# MCU3.net
KiCad netlist of a schematic drawn in Altium Designer
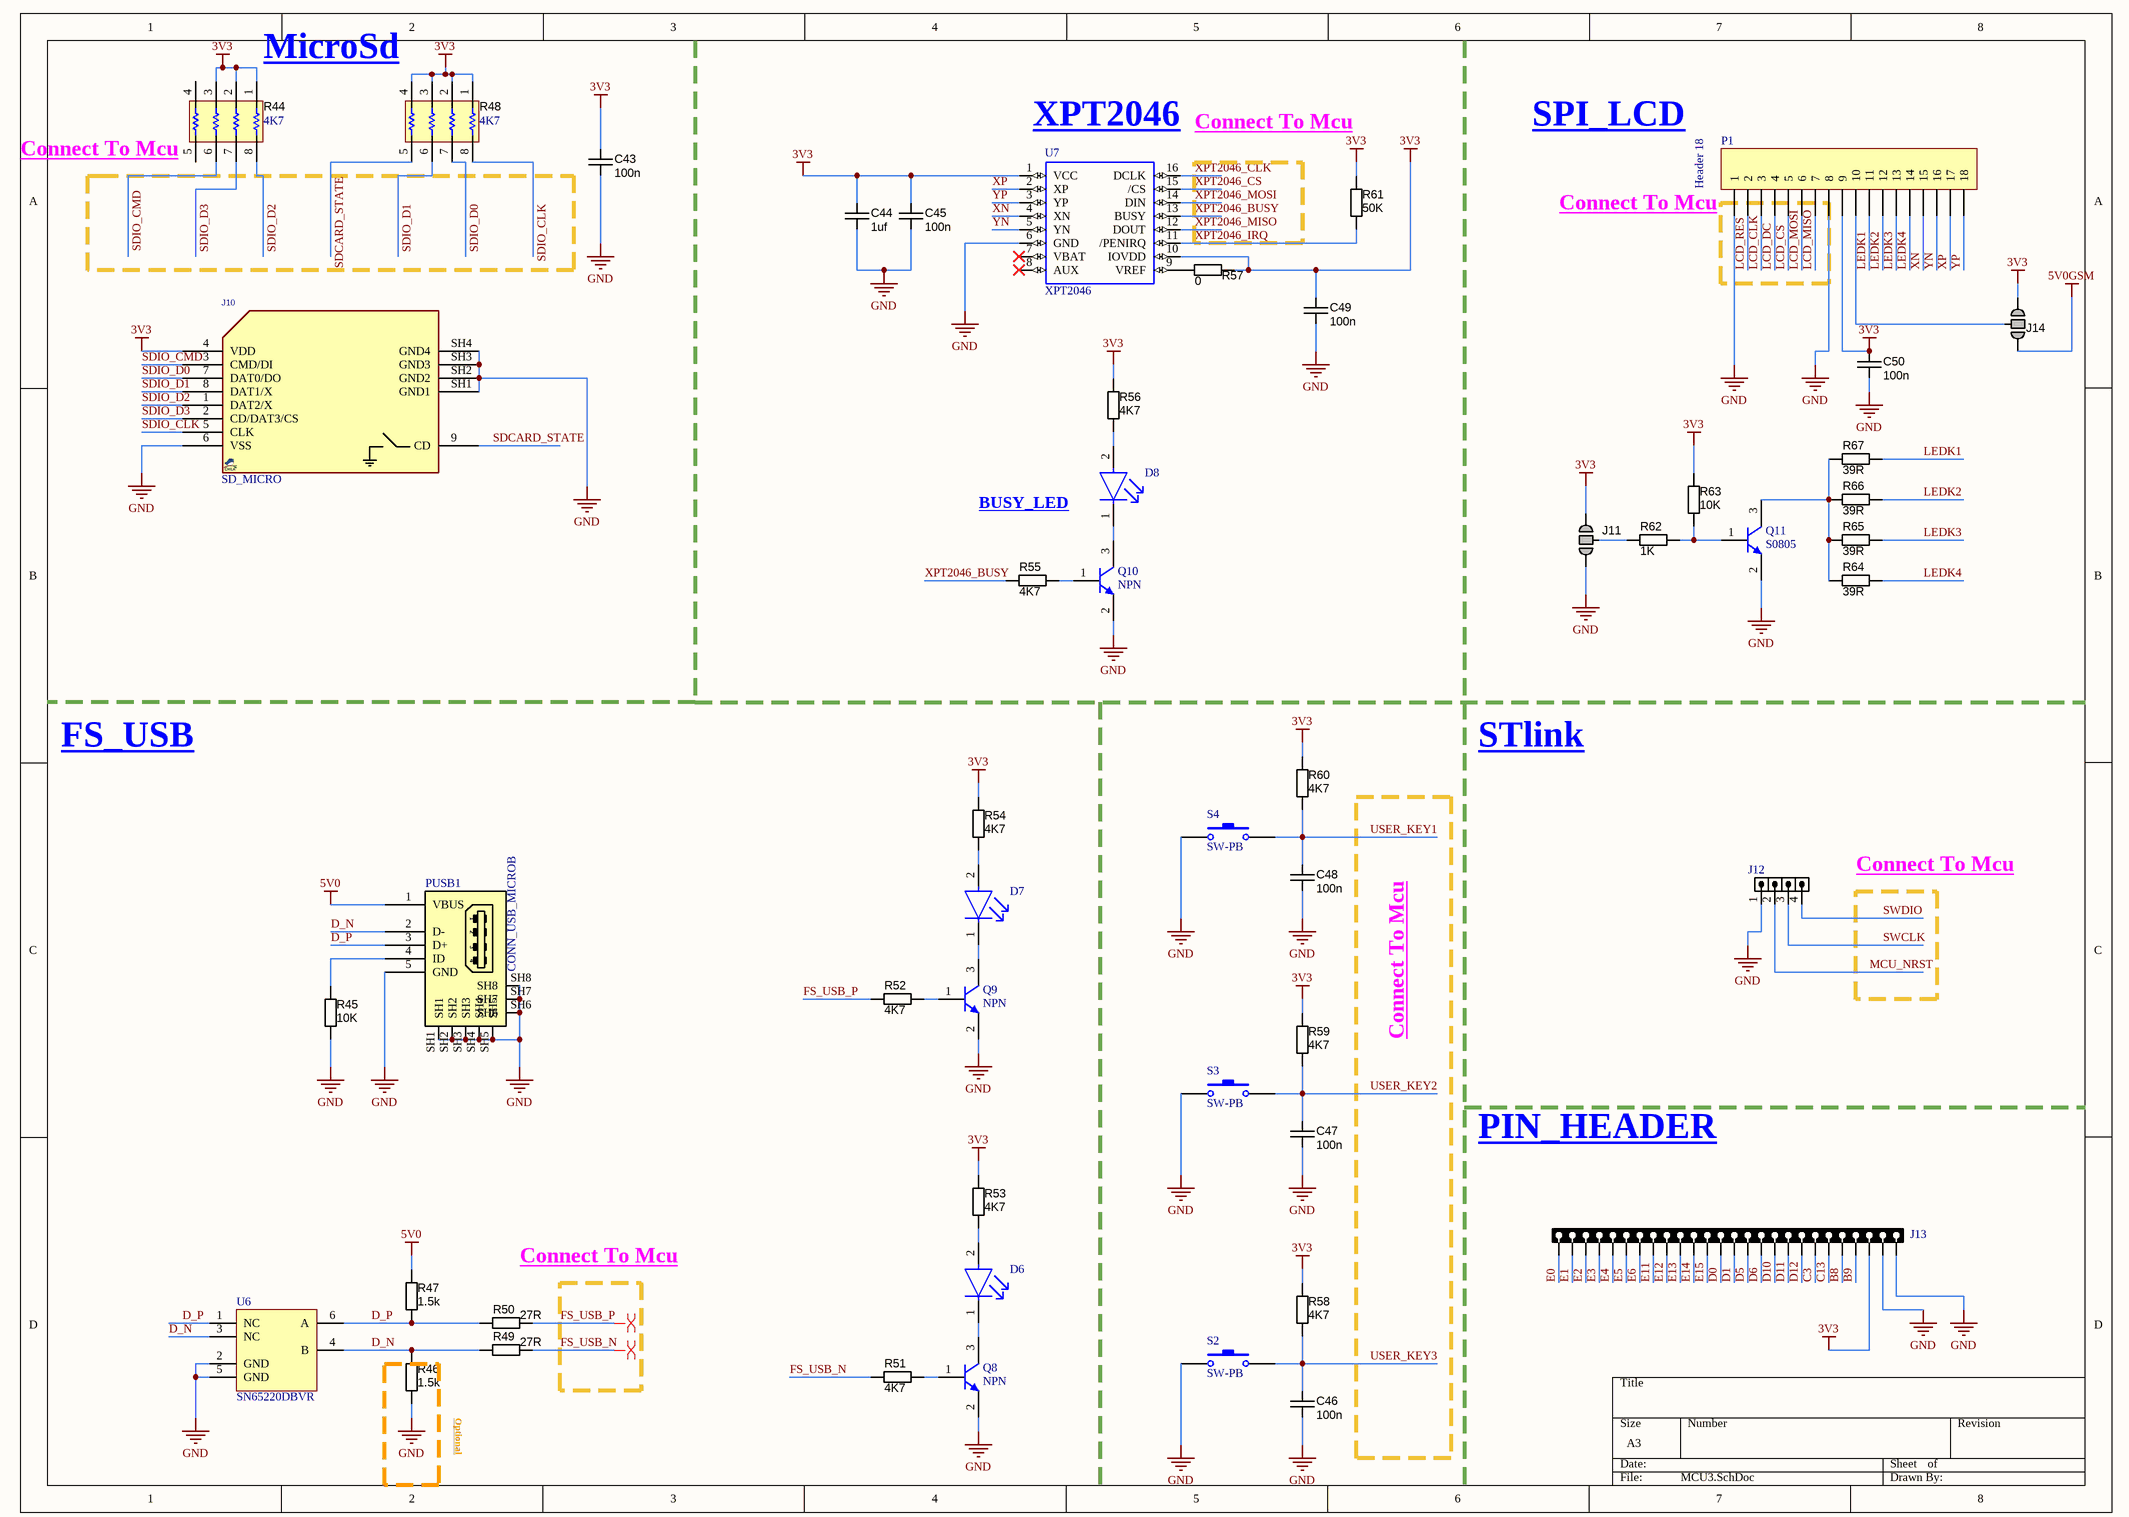
[diagram p0: MCU3.SchDoc]

(export (version "E")
  (design (tool "Eeschema 10.0.6"))
  (components
    (comp (ref "C43")
      (value "100n")
      (footprint "CAPC1608X90N")
      (description "Capacitor SMD Cer 100nF 10% 50V X7R 0603")
      (fields (field (name "TOLERANCE") "±10%") (field (name "Comment") "approved sub OK"))
      (libsource (lib "PBL - Capacitors") (part "CAPC_100n_0603_X7R_50V_10%"))
    )
    (comp (ref "C44")
      (value "1uf")
      (footprint "CAPC3216X180N")
      (description "Capacitor SMD Cer 47nF 10% 50V X7R 1206")
      (fields (field (name "TOLERANCE") "±10%"))
      (libsource (lib "PBL - Capacitors") (part "CAPC_47n_1206_X7R_50V_10%"))
    )
    (comp (ref "C45")
      (value "100n")
      (footprint "CAPC1608X90N")
      (description "Capacitor SMD Cer 100nF 10% 50V X7R 0603")
      (fields (field (name "TOLERANCE") "±10%") (field (name "Comment") "approved sub OK"))
      (libsource (lib "PBL - Capacitors") (part "CAPC_100n_0603_X7R_50V_10%"))
    )
    (comp (ref "C46")
      (value "100n")
      (footprint "CAPC1608X90N")
      (description "Capacitor SMD Cer 100nF 10% 50V X7R 0603")
      (fields (field (name "TOLERANCE") "±10%") (field (name "Comment") "approved sub OK"))
      (libsource (lib "PBL - Capacitors") (part "CAPC_100n_0603_X7R_50V_10%"))
    )
    (comp (ref "C47")
      (value "100n")
      (footprint "CAPC1608X90N")
      (description "Capacitor SMD Cer 100nF 10% 50V X7R 0603")
      (fields (field (name "TOLERANCE") "±10%") (field (name "Comment") "approved sub OK"))
      (libsource (lib "PBL - Capacitors") (part "CAPC_100n_0603_X7R_50V_10%"))
    )
    (comp (ref "C48")
      (value "100n")
      (footprint "CAPC1608X90N")
      (description "Capacitor SMD Cer 100nF 10% 50V X7R 0603")
      (fields (field (name "TOLERANCE") "±10%") (field (name "Comment") "approved sub OK"))
      (libsource (lib "PBL - Capacitors") (part "CAPC_100n_0603_X7R_50V_10%"))
    )
    (comp (ref "C49")
      (value "100n")
      (footprint "CAPC1608X90N")
      (description "Capacitor SMD Cer 100nF 10% 50V X7R 0603")
      (fields (field (name "TOLERANCE") "±10%") (field (name "Comment") "approved sub OK"))
      (libsource (lib "PBL - Capacitors") (part "CAPC_100n_0603_X7R_50V_10%"))
    )
    (comp (ref "C50")
      (value "100n")
      (footprint "CAPC1608X90N")
      (description "Capacitor SMD Cer 100nF 10% 50V X7R 0603")
      (fields (field (name "TOLERANCE") "±10%") (field (name "Comment") "approved sub OK"))
      (libsource (lib "PBL - Capacitors") (part "CAPC_100n_0603_X7R_50V_10%"))
    )
    (comp (ref "D6")
      (value "LTST-C191TBKT")
      (footprint "FP-LTST-C191TBKT-MFG")
      (description "LED BLUE CLEAR CHIP SMD")
      (libsource (lib "Altium Content Vault") (part "8706943c75ba83719d021d2fdc84c58"))
    )
    (comp (ref "D7")
      (value "LTST-C191TBKT")
      (footprint "FP-LTST-C191TBKT-MFG")
      (description "LED BLUE CLEAR CHIP SMD")
      (libsource (lib "Altium Content Vault") (part "8706943c75ba83719d021d2fdc84c58"))
    )
    (comp (ref "D8")
      (value "LTST-C191TBKT")
      (footprint "FP-LTST-C191TBKT-MFG")
      (description "LED BLUE CLEAR CHIP SMD")
      (libsource (lib "Altium Content Vault") (part "8706943c75ba83719d021d2fdc84c58"))
    )
    (comp (ref "J10")
      (value "SD_MICRO")
      (footprint "SDMICRO_AT")
      (description "SD MICRO exist in Iran, Attend 112J-TDAR-R01")
      (fields (field (name "MANF") "Attend") (field (name "MANF_P#") "112J-TDAR-R01"))
      (libsource (lib "socket_card") (part "SOCKET_SDMICRO_AT"))
    )
    (comp (ref "J11")
      (value "Jumper")
      (footprint "Jump_3Way")
      (description "SMD jumper")
      (libsource (lib "PBL - Pads and Jumpers") (part "JUMP_3WAY"))
    )
    (comp (ref "J12")
      (value "HDR1X4")
      (footprint "HDR1X4_2.54mmp")
      (description "CONN, HEADER, Male, pitch: 2.54mm, 4POS")
      (libsource (lib "conn_header_2.54_st") (part "HDR_M_1X4"))
    )
    (comp (ref "J13")
      (value "HDRF26")
      (footprint "HDR 1X26")
      (description "CONN, HEADER, Male, pitch: 2.54mm, 26POS")
      (libsource (lib "Header") (part "HDR_F_1X26"))
    )
    (comp (ref "J14")
      (value "Jumper")
      (footprint "Jump_3Way")
      (description "SMD jumper")
      (libsource (lib "PBL - Pads and Jumpers") (part "JUMP_3WAY"))
    )
    (comp (ref "P1")
      (value "Header 18")
      (footprint "SPI_LCD_18Pin")
      (description "Header, 18-Pin")
      (fields (field (name "PUBLISHER") "Altium Limited"))
      (libsource (lib "Miscellaneous Connectors") (part "Header 18"))
    )
    (comp (ref "PUSB1")
      (value "CONN_USB_MICROB")
      (footprint "USB_MICRO_B_BM_SHS")
      (description "CONN, USB, MICRO B, R/A, SMD, BOTTOM MOUNT")
      (fields (field (name "MANF_P#") "47491-0001") (field (name "MANF") "MOLEX"))
      (libsource (lib "conn_usb") (part "CONN_USB_MICRO_B_MOLEX"))
    )
    (comp (ref "Q8")
      (value "NPN")
      (footprint "SOT23-3")
      (description "NPN Bipolar Transistor")
      (fields (field (name "PUBLISHER") "Altium Limited"))
      (libsource (lib "Miscellaneous Devices") (part "NPN"))
    )
    (comp (ref "Q9")
      (value "NPN")
      (footprint "SOT23-3")
      (description "NPN Bipolar Transistor")
      (fields (field (name "PUBLISHER") "Altium Limited"))
      (libsource (lib "Miscellaneous Devices") (part "NPN"))
    )
    (comp (ref "Q10")
      (value "NPN")
      (footprint "SOT23-3")
      (description "NPN Bipolar Transistor")
      (fields (field (name "PUBLISHER") "Altium Limited"))
      (libsource (lib "Miscellaneous Devices") (part "NPN"))
    )
    (comp (ref "Q11")
      (value "S0805")
      (footprint "SOT23-3")
      (description "NPN Bipolar Transistor")
      (fields (field (name "PUBLISHER") "Altium Limited"))
      (libsource (lib "Miscellaneous Devices") (part "NPN"))
    )
    (comp (ref "R44")
      (value "4K7")
      (footprint "RP0603X4")
      (description "Resistor Array SMD")
      (libsource (lib "Resistor") (part "Resistor Array SMD"))
    )
    (comp (ref "R45")
      (value "10K")
      (footprint "RESC1608X55N")
      (description "Resistor SMD chip 10K Ohm 0.1W 5% 0603")
      (fields (field (name "TOLERANCE") "±5%") (field (name "Comment") "Thick Film"))
      (libsource (lib "PBL - Resistors") (part "RES_4K7_0603_5%"))
    )
    (comp (ref "R46")
      (value "1.5k")
      (footprint "RESC1608X55N")
      (description "Resistor SMD chip 1.5k Ohm 0.1W 5% 0603")
      (fields (field (name "TOLERANCE") "±5%") (field (name "Comment") "Thick Film"))
      (libsource (lib "") (part "RES_4K7_0603_5%_2"))
    )
    (comp (ref "R47")
      (value "1.5k")
      (footprint "RESC1608X55N")
      (description "Resistor SMD chip 1.5k Ohm 0.1W 5% 0603")
      (fields (field (name "TOLERANCE") "±5%") (field (name "Comment") "Thick Film"))
      (libsource (lib "") (part "RES_4K7_0603_5%_2"))
    )
    (comp (ref "R48")
      (value "4K7")
      (footprint "RP0603X4")
      (description "Resistor Array SMD")
      (libsource (lib "Resistor") (part "Resistor Array SMD"))
    )
    (comp (ref "R49")
      (value "27R")
      (footprint "RESC1608X55N")
      (description "Resistor SMD chip 27 Ohm 0.1W 5% 0603")
      (fields (field (name "TOLERANCE") "±5%") (field (name "Comment") "Thick Film"))
      (libsource (lib "PBL - Resistors") (part "RES_4K7_0603_5%"))
    )
    (comp (ref "R50")
      (value "27R")
      (footprint "RESC1608X55N")
      (description "Resistor SMD chip 27 Ohm 0.1W 5% 0603")
      (fields (field (name "TOLERANCE") "±5%") (field (name "Comment") "Thick Film"))
      (libsource (lib "PBL - Resistors") (part "RES_4K7_0603_5%"))
    )
    (comp (ref "R51")
      (value "4K7")
      (footprint "RESC1608X55N")
      (description "Resistor SMD chip 4.7k Ohm 0.1W 5% 0603")
      (fields (field (name "TOLERANCE") "±5%") (field (name "Comment") "Thick Film"))
      (libsource (lib "") (part "RES_4K7_0603_5%_1"))
    )
    (comp (ref "R52")
      (value "4K7")
      (footprint "RESC1608X55N")
      (description "Resistor SMD chip 4.7k Ohm 0.1W 5% 0603")
      (fields (field (name "TOLERANCE") "±5%") (field (name "Comment") "Thick Film"))
      (libsource (lib "") (part "RES_4K7_0603_5%_1"))
    )
    (comp (ref "R53")
      (value "4K7")
      (footprint "RESC1608X55N")
      (description "Resistor SMD chip 4.7k Ohm 0.1W 5% 0603")
      (fields (field (name "TOLERANCE") "±5%") (field (name "Comment") "Thick Film"))
      (libsource (lib "PBL - Resistors") (part "RES_4K7_0603_5%"))
    )
    (comp (ref "R54")
      (value "4K7")
      (footprint "RESC1608X55N")
      (description "Resistor SMD chip 4.7k Ohm 0.1W 5% 0603")
      (fields (field (name "TOLERANCE") "±5%") (field (name "Comment") "Thick Film"))
      (libsource (lib "PBL - Resistors") (part "RES_4K7_0603_5%"))
    )
    (comp (ref "R55")
      (value "4K7")
      (footprint "RESC1608X55N")
      (description "Resistor SMD chip 4.7k Ohm 0.1W 5% 0603")
      (fields (field (name "TOLERANCE") "±5%") (field (name "Comment") "Thick Film"))
      (libsource (lib "") (part "RES_4K7_0603_5%_1"))
    )
    (comp (ref "R56")
      (value "4K7")
      (footprint "RESC1608X55N")
      (description "Resistor SMD chip 4.7k Ohm 0.1W 5% 0603")
      (fields (field (name "TOLERANCE") "±5%") (field (name "Comment") "Thick Film"))
      (libsource (lib "PBL - Resistors") (part "RES_4K7_0603_5%"))
    )
    (comp (ref "R57")
      (value "0")
      (footprint "RESC1608X55N")
      (description "Resistor SMD chip 0 Ohm 0.1W 5% 0603")
      (fields (field (name "TOLERANCE") "±5%") (field (name "Comment") "Thick Film"))
      (libsource (lib "") (part "RES_4K7_0603_5%_2"))
    )
    (comp (ref "R58")
      (value "4K7")
      (footprint "RESC1608X55N")
      (description "Resistor SMD chip 4.7k Ohm 0.1W 5% 0603")
      (fields (field (name "TOLERANCE") "±5%") (field (name "Comment") "Thick Film"))
      (libsource (lib "") (part "RES_4K7_0603_5%_2"))
    )
    (comp (ref "R59")
      (value "4K7")
      (footprint "RESC1608X55N")
      (description "Resistor SMD chip 4.7k Ohm 0.1W 5% 0603")
      (fields (field (name "TOLERANCE") "±5%") (field (name "Comment") "Thick Film"))
      (libsource (lib "") (part "RES_4K7_0603_5%_2"))
    )
    (comp (ref "R60")
      (value "4K7")
      (footprint "RESC1608X55N")
      (description "Resistor SMD chip 4.7k Ohm 0.1W 5% 0603")
      (fields (field (name "TOLERANCE") "±5%") (field (name "Comment") "Thick Film"))
      (libsource (lib "") (part "RES_4K7_0603_5%_2"))
    )
    (comp (ref "R61")
      (value "50K")
      (footprint "RESC1608X55N")
      (description "Resistor SMD chip 10K Ohm 0.1W 5% 0603")
      (fields (field (name "TOLERANCE") "±5%") (field (name "Comment") "Thick Film"))
      (libsource (lib "") (part "RES_4K7_0603_5%_3"))
    )
    (comp (ref "R62")
      (value "1K")
      (footprint "RESC1608X55N")
      (description "Resistor SMD chip 1K Ohm 0.1W 5% 0603")
      (fields (field (name "TOLERANCE") "±5%") (field (name "Comment") "Thick Film"))
      (libsource (lib "") (part "RES_4K7_0603_5%_2"))
    )
    (comp (ref "R63")
      (value "10K")
      (footprint "RESC1608X55N")
      (description "Resistor SMD chip 10K Ohm 0.1W 5% 0603")
      (fields (field (name "TOLERANCE") "±5%") (field (name "Comment") "Thick Film"))
      (libsource (lib "PBL - Resistors") (part "RES_4K7_0603_5%"))
    )
    (comp (ref "R64")
      (value "39R")
      (footprint "RESC1608X55N")
      (description "Resistor SMD chip 39R Ohm 0.1W 5% 0603")
      (fields (field (name "TOLERANCE") "±5%") (field (name "Comment") "Thick Film"))
      (libsource (lib "") (part "RES_4K7_0603_5%_1"))
    )
    (comp (ref "R65")
      (value "39R")
      (footprint "RESC1608X55N")
      (description "Resistor SMD chip 39R Ohm 0.1W 5% 0603")
      (fields (field (name "TOLERANCE") "±5%") (field (name "Comment") "Thick Film"))
      (libsource (lib "") (part "RES_4K7_0603_5%_1"))
    )
    (comp (ref "R66")
      (value "39R")
      (footprint "RESC1608X55N")
      (description "Resistor SMD chip 39R Ohm 0.1W 5% 0603")
      (fields (field (name "TOLERANCE") "±5%") (field (name "Comment") "Thick Film"))
      (libsource (lib "") (part "RES_4K7_0603_5%_1"))
    )
    (comp (ref "R67")
      (value "39R")
      (footprint "RESC1608X55N")
      (description "Resistor SMD chip 39R Ohm 0.1W 5% 0603")
      (fields (field (name "TOLERANCE") "±5%") (field (name "Comment") "Thick Film"))
      (libsource (lib "") (part "RES_4K7_0603_5%_1"))
    )
    (comp (ref "S2")
      (value "SW-PB")
      (footprint "SWPBS_SPST_6X3X5")
      (description "Switch")
      (fields (field (name "PUBLISHER") "Altium Limited"))
      (libsource (lib "Miscellaneous Devices") (part "SW-PB"))
    )
    (comp (ref "S3")
      (value "SW-PB")
      (footprint "SWPBS_SPST_6X3X5")
      (description "Switch")
      (fields (field (name "PUBLISHER") "Altium Limited"))
      (libsource (lib "Miscellaneous Devices") (part "SW-PB"))
    )
    (comp (ref "S4")
      (value "SW-PB")
      (footprint "SWPBS_SPST_6X3X5")
      (description "Switch")
      (fields (field (name "PUBLISHER") "Altium Limited"))
      (libsource (lib "Miscellaneous Devices") (part "SW-PB"))
    )
    (comp (ref "U6")
      (value "SN65220DBVR")
      (footprint "DBV0006A_M")
      (fields (field (name "MANUFACTURER") "Texas Instruments"))
      (libsource (lib "Altium Content Vault") (part "TI-SN65220-SOT-23_DBV-6"))
    )
    (comp (ref "U7")
      (value "XPT2046")
      (footprint "TSSOP16")
      (description "RASPBERRY PI 3.5 TFT DISPLAY")
      (fields (field (name "MF") "Xptek"))
      (libsource (lib "XPT2046") (part "XPT2046"))
    )
  )
  (nets
    (net (code "2") (name "/B8") (class "Default")
      (node (ref "J13") (pin "22") (pinfunction "22_22") (pintype "passive"))
    )
    (net (code "3") (name "/B9") (class "Default")
      (node (ref "J13") (pin "23") (pinfunction "23_23") (pintype "passive"))
    )
    (net (code "4") (name "/C3") (class "Default")
      (node (ref "J13") (pin "20") (pinfunction "20_20") (pintype "passive"))
    )
    (net (code "5") (name "/C13") (class "Default")
      (node (ref "J13") (pin "21") (pinfunction "21_21") (pintype "passive"))
    )
    (net (code "6") (name "/D0") (class "Default")
      (node (ref "J13") (pin "13") (pinfunction "13_13") (pintype "passive"))
    )
    (net (code "7") (name "/D1") (class "Default")
      (node (ref "J13") (pin "14") (pinfunction "14_14") (pintype "passive"))
    )
    (net (code "8") (name "/D5") (class "Default")
      (node (ref "J13") (pin "15") (pinfunction "15_15") (pintype "passive"))
    )
    (net (code "9") (name "/D6") (class "Default")
      (node (ref "J13") (pin "16") (pinfunction "16_16") (pintype "passive"))
    )
    (net (code "10") (name "/D10") (class "Default")
      (node (ref "J13") (pin "17") (pinfunction "17_17") (pintype "passive"))
    )
    (net (code "11") (name "/D11") (class "Default")
      (node (ref "J13") (pin "18") (pinfunction "18_18") (pintype "passive"))
    )
    (net (code "12") (name "/D12") (class "Default")
      (node (ref "J13") (pin "19") (pinfunction "19_19") (pintype "passive"))
    )
    (net (code "13") (name "/D_N") (class "Default")
      (node (ref "PUSB1") (pin "2") (pinfunction "D-_2") (pintype "passive"))
      (node (ref "R46") (pin "1") (pinfunction "1_1") (pintype "passive"))
      (node (ref "R49") (pin "1") (pinfunction "1_1") (pintype "passive"))
      (node (ref "U6") (pin "3") (pinfunction "NC_3") (pintype "passive"))
      (node (ref "U6") (pin "4") (pinfunction "B_4") (pintype "passive"))
    )
    (net (code "14") (name "/D_P") (class "Default")
      (node (ref "PUSB1") (pin "3") (pinfunction "D+_3") (pintype "passive"))
      (node (ref "R47") (pin "2") (pinfunction "2_2") (pintype "passive"))
      (node (ref "R50") (pin "1") (pinfunction "1_1") (pintype "passive"))
      (node (ref "U6") (pin "1") (pinfunction "NC_1") (pintype "passive"))
      (node (ref "U6") (pin "6") (pinfunction "A_6") (pintype "passive"))
    )
    (net (code "15") (name "/E0") (class "Default")
      (node (ref "J13") (pin "1") (pinfunction "1_1") (pintype "passive"))
    )
    (net (code "16") (name "/E1") (class "Default")
      (node (ref "J13") (pin "2") (pinfunction "2_2") (pintype "passive"))
    )
    (net (code "17") (name "/E2") (class "Default")
      (node (ref "J13") (pin "3") (pinfunction "3_3") (pintype "passive"))
    )
    (net (code "18") (name "/E3") (class "Default")
      (node (ref "J13") (pin "4") (pinfunction "4_4") (pintype "passive"))
    )
    (net (code "19") (name "/E4") (class "Default")
      (node (ref "J13") (pin "5") (pinfunction "5_5") (pintype "passive"))
    )
    (net (code "20") (name "/E5") (class "Default")
      (node (ref "J13") (pin "6") (pinfunction "6_6") (pintype "passive"))
    )
    (net (code "21") (name "/E6") (class "Default")
      (node (ref "J13") (pin "7") (pinfunction "7_7") (pintype "passive"))
    )
    (net (code "22") (name "/E11") (class "Default")
      (node (ref "J13") (pin "8") (pinfunction "8_8") (pintype "passive"))
    )
    (net (code "23") (name "/E12") (class "Default")
      (node (ref "J13") (pin "9") (pinfunction "9_9") (pintype "passive"))
    )
    (net (code "24") (name "/E13") (class "Default")
      (node (ref "J13") (pin "10") (pinfunction "10_10") (pintype "passive"))
    )
    (net (code "25") (name "/E14") (class "Default")
      (node (ref "J13") (pin "11") (pinfunction "11_11") (pintype "passive"))
    )
    (net (code "26") (name "/E15") (class "Default")
      (node (ref "J13") (pin "12") (pinfunction "12_12") (pintype "passive"))
    )
    (net (code "27") (name "/FS_USB_N") (class "Default")
      (node (ref "R49") (pin "2") (pinfunction "2_2") (pintype "passive"))
      (node (ref "R51") (pin "1") (pinfunction "1_1") (pintype "passive"))
    )
    (net (code "28") (name "/FS_USB_P") (class "Default")
      (node (ref "R50") (pin "2") (pinfunction "2_2") (pintype "passive"))
      (node (ref "R52") (pin "1") (pinfunction "1_1") (pintype "passive"))
    )
    (net (code "29") (name "/LCD_CLK") (class "Default")
      (node (ref "P1") (pin "3") (pinfunction "3_3") (pintype "passive"))
    )
    (net (code "30") (name "/LCD_CS") (class "Default")
      (node (ref "P1") (pin "5") (pinfunction "5_5") (pintype "passive"))
    )
    (net (code "31") (name "/LCD_DC") (class "Default")
      (node (ref "P1") (pin "4") (pinfunction "4_4") (pintype "passive"))
    )
    (net (code "32") (name "/LCD_MISO") (class "Default")
      (node (ref "P1") (pin "7") (pinfunction "7_7") (pintype "passive"))
    )
    (net (code "33") (name "/LCD_MOSI") (class "Default")
      (node (ref "P1") (pin "6") (pinfunction "6_6") (pintype "passive"))
    )
    (net (code "34") (name "/LCD_RES") (class "Default")
      (node (ref "P1") (pin "2") (pinfunction "2_2") (pintype "passive"))
    )
    (net (code "35") (name "/LEDK1") (class "Default")
      (node (ref "P1") (pin "11") (pinfunction "11_11") (pintype "passive"))
      (node (ref "R67") (pin "2") (pinfunction "2_2") (pintype "passive"))
    )
    (net (code "36") (name "/LEDK2") (class "Default")
      (node (ref "P1") (pin "12") (pinfunction "12_12") (pintype "passive"))
      (node (ref "R66") (pin "2") (pinfunction "2_2") (pintype "passive"))
    )
    (net (code "37") (name "/LEDK3") (class "Default")
      (node (ref "P1") (pin "13") (pinfunction "13_13") (pintype "passive"))
      (node (ref "R65") (pin "2") (pinfunction "2_2") (pintype "passive"))
    )
    (net (code "38") (name "/LEDK4") (class "Default")
      (node (ref "P1") (pin "14") (pinfunction "14_14") (pintype "passive"))
      (node (ref "R64") (pin "2") (pinfunction "2_2") (pintype "passive"))
    )
    (net (code "39") (name "/MCU_NRST") (class "Default")
      (node (ref "J12") (pin "2") (pinfunction "2_2") (pintype "passive"))
    )
    (net (code "40") (name "/SDCARD_STATE") (class "Default")
      (node (ref "J10") (pin "9") (pinfunction "CD_9") (pintype "passive"))
      (node (ref "R48") (pin "5") (pinfunction "5_5") (pintype "passive"))
    )
    (net (code "41") (name "/SDIO_CLK") (class "Default")
      (node (ref "J10") (pin "5") (pinfunction "CLK_5") (pintype "passive"))
      (node (ref "R48") (pin "8") (pinfunction "8_8") (pintype "passive"))
    )
    (net (code "42") (name "/SDIO_CMD") (class "Default")
      (node (ref "J10") (pin "3") (pinfunction "CMD/DI_3") (pintype "passive"))
      (node (ref "R44") (pin "6") (pinfunction "6_6") (pintype "passive"))
    )
    (net (code "43") (name "/SDIO_D0") (class "Default")
      (node (ref "J10") (pin "7") (pinfunction "DAT0/DO_7") (pintype "passive"))
      (node (ref "R48") (pin "7") (pinfunction "7_7") (pintype "passive"))
    )
    (net (code "44") (name "/SDIO_D1") (class "Default")
      (node (ref "J10") (pin "8") (pinfunction "DAT1/X_8") (pintype "passive"))
      (node (ref "R48") (pin "6") (pinfunction "6_6") (pintype "passive"))
    )
    (net (code "45") (name "/SDIO_D2") (class "Default")
      (node (ref "J10") (pin "1") (pinfunction "DAT2/X_1") (pintype "passive"))
      (node (ref "R44") (pin "8") (pinfunction "8_8") (pintype "passive"))
    )
    (net (code "46") (name "/SDIO_D3") (class "Default")
      (node (ref "J10") (pin "2") (pinfunction "CD/DAT3/CS_2") (pintype "passive"))
      (node (ref "R44") (pin "7") (pinfunction "7_7") (pintype "passive"))
    )
    (net (code "47") (name "/SWCLK") (class "Default")
      (node (ref "J12") (pin "3") (pinfunction "3_3") (pintype "passive"))
    )
    (net (code "48") (name "/SWDIO") (class "Default")
      (node (ref "J12") (pin "4") (pinfunction "4_4") (pintype "passive"))
    )
    (net (code "49") (name "/USER_KEY1") (class "Default")
      (node (ref "C48") (pin "1") (pintype "passive"))
      (node (ref "R60") (pin "2") (pinfunction "2_2") (pintype "passive"))
      (node (ref "S4") (pin "1") (pinfunction "1_1") (pintype "passive"))
    )
    (net (code "50") (name "/USER_KEY2") (class "Default")
      (node (ref "C47") (pin "1") (pintype "passive"))
      (node (ref "R59") (pin "2") (pinfunction "2_2") (pintype "passive"))
      (node (ref "S3") (pin "1") (pinfunction "1_1") (pintype "passive"))
    )
    (net (code "51") (name "/USER_KEY3") (class "Default")
      (node (ref "C46") (pin "1") (pintype "passive"))
      (node (ref "R58") (pin "2") (pinfunction "2_2") (pintype "passive"))
      (node (ref "S2") (pin "1") (pinfunction "1_1") (pintype "passive"))
    )
    (net (code "52") (name "/XN") (class "Default")
      (node (ref "P1") (pin "15") (pinfunction "15_15") (pintype "passive"))
      (node (ref "U7") (pin "4") (pinfunction "XN_4") (pintype "bidirectional"))
    )
    (net (code "53") (name "/XP") (class "Default")
      (node (ref "P1") (pin "17") (pinfunction "17_17") (pintype "passive"))
      (node (ref "U7") (pin "2") (pinfunction "XP_2") (pintype "bidirectional"))
    )
    (net (code "54") (name "/XPT2046_BUSY") (class "Default")
      (node (ref "R55") (pin "1") (pinfunction "1_1") (pintype "passive"))
      (node (ref "U7") (pin "13") (pinfunction "BUSY_13") (pintype "bidirectional"))
    )
    (net (code "55") (name "/XPT2046_CLK") (class "Default")
      (node (ref "U7") (pin "16") (pinfunction "DCLK_16") (pintype "bidirectional"))
    )
    (net (code "56") (name "/XPT2046_CS") (class "Default")
      (node (ref "U7") (pin "15") (pinfunction "/CS_15") (pintype "bidirectional"))
    )
    (net (code "57") (name "/XPT2046_IRQ") (class "Default")
      (node (ref "R61") (pin "2") (pinfunction "2_2") (pintype "passive"))
      (node (ref "U7") (pin "11") (pinfunction "/PENIRQ_11") (pintype "bidirectional"))
    )
    (net (code "58") (name "/XPT2046_MISO") (class "Default")
      (node (ref "U7") (pin "12") (pinfunction "DOUT_12") (pintype "bidirectional"))
    )
    (net (code "59") (name "/XPT2046_MOSI") (class "Default")
      (node (ref "U7") (pin "14") (pinfunction "DIN_14") (pintype "bidirectional"))
    )
    (net (code "60") (name "/YN") (class "Default")
      (node (ref "P1") (pin "16") (pinfunction "16_16") (pintype "passive"))
      (node (ref "U7") (pin "5") (pinfunction "YN_5") (pintype "bidirectional"))
    )
    (net (code "61") (name "/YP") (class "Default")
      (node (ref "P1") (pin "18") (pinfunction "18_18") (pintype "passive"))
      (node (ref "U7") (pin "3") (pinfunction "YP_3") (pintype "bidirectional"))
    )
    (net (code "62") (name "3V3") (class "Default")
      (node (ref "C43") (pin "1") (pintype "passive"))
      (node (ref "C44") (pin "1") (pintype "passive"))
      (node (ref "C45") (pin "1") (pintype "passive"))
      (node (ref "C49") (pin "1") (pintype "passive"))
      (node (ref "C50") (pin "1") (pintype "passive"))
      (node (ref "J10") (pin "4") (pinfunction "VDD_4") (pintype "passive"))
      (node (ref "J11") (pin "3") (pinfunction "3_3") (pintype "passive"))
      (node (ref "J13") (pin "24") (pinfunction "24_24") (pintype "passive"))
      (node (ref "J14") (pin "1") (pinfunction "1_1") (pintype "passive"))
      (node (ref "P1") (pin "9") (pinfunction "9_9") (pintype "passive"))
      (node (ref "R44") (pin "1") (pinfunction "1_1") (pintype "passive"))
      (node (ref "R44") (pin "2") (pinfunction "2_2") (pintype "passive"))
      (node (ref "R44") (pin "3") (pinfunction "3_3") (pintype "passive"))
      (node (ref "R48") (pin "1") (pinfunction "1_1") (pintype "passive"))
      (node (ref "R48") (pin "2") (pinfunction "2_2") (pintype "passive"))
      (node (ref "R48") (pin "3") (pinfunction "3_3") (pintype "passive"))
      (node (ref "R48") (pin "4") (pinfunction "4_4") (pintype "passive"))
      (node (ref "R53") (pin "2") (pinfunction "2_2") (pintype "passive"))
      (node (ref "R54") (pin "2") (pinfunction "2_2") (pintype "passive"))
      (node (ref "R56") (pin "2") (pinfunction "2_2") (pintype "passive"))
      (node (ref "R57") (pin "1") (pinfunction "1_1") (pintype "passive"))
      (node (ref "R58") (pin "1") (pinfunction "1_1") (pintype "passive"))
      (node (ref "R59") (pin "1") (pinfunction "1_1") (pintype "passive"))
      (node (ref "R60") (pin "1") (pinfunction "1_1") (pintype "passive"))
      (node (ref "R61") (pin "1") (pinfunction "1_1") (pintype "passive"))
      (node (ref "R63") (pin "2") (pinfunction "2_2") (pintype "passive"))
      (node (ref "U7") (pin "1") (pinfunction "VCC_1") (pintype "bidirectional"))
      (node (ref "U7") (pin "10") (pinfunction "IOVDD_10") (pintype "bidirectional"))
    )
    (net (code "63") (name "5V0") (class "Default")
      (node (ref "PUSB1") (pin "1") (pinfunction "VBUS_1") (pintype "power_in"))
      (node (ref "R47") (pin "1") (pinfunction "1_1") (pintype "passive"))
    )
    (net (code "64") (name "5V0GSM") (class "Default")
      (node (ref "J14") (pin "3") (pinfunction "3_3") (pintype "passive"))
    )
    (net (code "65") (name "GND") (class "Default")
      (node (ref "C43") (pin "2") (pintype "passive"))
      (node (ref "C44") (pin "2") (pintype "passive"))
      (node (ref "C45") (pin "2") (pintype "passive"))
      (node (ref "C46") (pin "2") (pintype "passive"))
      (node (ref "C47") (pin "2") (pintype "passive"))
      (node (ref "C48") (pin "2") (pintype "passive"))
      (node (ref "C49") (pin "2") (pintype "passive"))
      (node (ref "C50") (pin "2") (pintype "passive"))
      (node (ref "J10") (pin "6") (pinfunction "VSS_6") (pintype "passive"))
      (node (ref "J10") (pin "SH1") (pinfunction "GND1_SH1") (pintype "passive"))
      (node (ref "J10") (pin "SH2") (pinfunction "GND2_SH2") (pintype "passive"))
      (node (ref "J10") (pin "SH3") (pinfunction "GND3_SH3") (pintype "passive"))
      (node (ref "J10") (pin "SH4") (pinfunction "GND4_SH4") (pintype "passive"))
      (node (ref "J11") (pin "1") (pinfunction "1_1") (pintype "passive"))
      (node (ref "J12") (pin "1") (pinfunction "1_1") (pintype "passive"))
      (node (ref "J13") (pin "25") (pinfunction "25_25") (pintype "passive"))
      (node (ref "J13") (pin "26") (pinfunction "26_26") (pintype "passive"))
      (node (ref "P1") (pin "1") (pinfunction "1_1") (pintype "passive"))
      (node (ref "P1") (pin "8") (pinfunction "8_8") (pintype "passive"))
      (node (ref "PUSB1") (pin "5") (pinfunction "GND_5") (pintype "power_in"))
      (node (ref "PUSB1") (pin "SH1") (pinfunction "SH1_SH1") (pintype "passive"))
      (node (ref "PUSB1") (pin "SH2") (pinfunction "SH2_SH2") (pintype "passive"))
      (node (ref "PUSB1") (pin "SH3") (pinfunction "SH3_SH3") (pintype "passive"))
      (node (ref "PUSB1") (pin "SH4") (pinfunction "SH4_SH4") (pintype "passive"))
      (node (ref "PUSB1") (pin "SH5") (pinfunction "SH5_SH5") (pintype "passive"))
      (node (ref "PUSB1") (pin "SH6") (pinfunction "SH6_SH6") (pintype "passive"))
      (node (ref "PUSB1") (pin "SH7") (pinfunction "SH7_SH7") (pintype "passive"))
      (node (ref "PUSB1") (pin "SH8") (pinfunction "SH8_SH8") (pintype "passive"))
      (node (ref "Q10") (pin "2") (pinfunction "E_2") (pintype "passive"))
      (node (ref "Q11") (pin "2") (pinfunction "E_2") (pintype "passive"))
      (node (ref "Q8") (pin "2") (pinfunction "E_2") (pintype "passive"))
      (node (ref "Q9") (pin "2") (pinfunction "E_2") (pintype "passive"))
      (node (ref "R45") (pin "1") (pinfunction "1_1") (pintype "passive"))
      (node (ref "R46") (pin "2") (pinfunction "2_2") (pintype "passive"))
      (node (ref "S2") (pin "2") (pinfunction "2_2") (pintype "passive"))
      (node (ref "S3") (pin "2") (pinfunction "2_2") (pintype "passive"))
      (node (ref "S4") (pin "2") (pinfunction "2_2") (pintype "passive"))
      (node (ref "U6") (pin "2") (pinfunction "GND_2") (pintype "power_in"))
      (node (ref "U6") (pin "5") (pinfunction "GND_5") (pintype "power_in"))
      (node (ref "U7") (pin "6") (pinfunction "GND_6") (pintype "bidirectional"))
    )
    (net (code "66") (name "Net-(D6-A)") (class "Default")
      (node (ref "D6") (pin "2") (pinfunction "A_2") (pintype "passive"))
      (node (ref "R53") (pin "1") (pinfunction "1_1") (pintype "passive"))
    )
    (net (code "67") (name "Net-(D6-C)") (class "Default")
      (node (ref "D6") (pin "1") (pinfunction "C_1") (pintype "passive"))
      (node (ref "Q8") (pin "3") (pinfunction "C_3") (pintype "passive"))
    )
    (net (code "68") (name "Net-(D7-A)") (class "Default")
      (node (ref "D7") (pin "2") (pinfunction "A_2") (pintype "passive"))
      (node (ref "R54") (pin "1") (pinfunction "1_1") (pintype "passive"))
    )
    (net (code "69") (name "Net-(D7-C)") (class "Default")
      (node (ref "D7") (pin "1") (pinfunction "C_1") (pintype "passive"))
      (node (ref "Q9") (pin "3") (pinfunction "C_3") (pintype "passive"))
    )
    (net (code "70") (name "Net-(D8-A)") (class "Default")
      (node (ref "D8") (pin "2") (pinfunction "A_2") (pintype "passive"))
      (node (ref "R56") (pin "1") (pinfunction "1_1") (pintype "passive"))
    )
    (net (code "71") (name "Net-(D8-C)") (class "Default")
      (node (ref "D8") (pin "1") (pinfunction "C_1") (pintype "passive"))
      (node (ref "Q10") (pin "3") (pinfunction "C_3") (pintype "passive"))
    )
    (net (code "72") (name "Net-(J11-Pad2)") (class "Default")
      (node (ref "J11") (pin "2") (pinfunction "2_2") (pintype "passive"))
      (node (ref "R62") (pin "2") (pinfunction "2_2") (pintype "passive"))
    )
    (net (code "73") (name "Net-(J14-Pad2)") (class "Default")
      (node (ref "J14") (pin "2") (pinfunction "2_2") (pintype "passive"))
      (node (ref "P1") (pin "10") (pinfunction "10_10") (pintype "passive"))
    )
    (net (code "74") (name "Net-(PUSB1-ID)") (class "Default")
      (node (ref "PUSB1") (pin "4") (pinfunction "ID_4") (pintype "power_in"))
      (node (ref "R45") (pin "2") (pinfunction "2_2") (pintype "passive"))
    )
    (net (code "75") (name "Net-(Q8-B)") (class "Default")
      (node (ref "Q8") (pin "1") (pinfunction "B_1") (pintype "passive"))
      (node (ref "R51") (pin "2") (pinfunction "2_2") (pintype "passive"))
    )
    (net (code "76") (name "Net-(Q9-B)") (class "Default")
      (node (ref "Q9") (pin "1") (pinfunction "B_1") (pintype "passive"))
      (node (ref "R52") (pin "2") (pinfunction "2_2") (pintype "passive"))
    )
    (net (code "77") (name "Net-(Q10-B)") (class "Default")
      (node (ref "Q10") (pin "1") (pinfunction "B_1") (pintype "passive"))
      (node (ref "R55") (pin "2") (pinfunction "2_2") (pintype "passive"))
    )
    (net (code "78") (name "Net-(Q11-B)") (class "Default")
      (node (ref "Q11") (pin "1") (pinfunction "B_1") (pintype "passive"))
      (node (ref "R62") (pin "1") (pinfunction "1_1") (pintype "passive"))
      (node (ref "R63") (pin "1") (pinfunction "1_1") (pintype "passive"))
    )
    (net (code "79") (name "Net-(Q11-C)") (class "Default")
      (node (ref "Q11") (pin "3") (pinfunction "C_3") (pintype "passive"))
      (node (ref "R64") (pin "1") (pinfunction "1_1") (pintype "passive"))
      (node (ref "R65") (pin "1") (pinfunction "1_1") (pintype "passive"))
      (node (ref "R66") (pin "1") (pinfunction "1_1") (pintype "passive"))
      (node (ref "R67") (pin "1") (pinfunction "1_1") (pintype "passive"))
    )
    (net (code "80") (name "Net-(U7-VREF)") (class "Default")
      (node (ref "R57") (pin "2") (pinfunction "2_2") (pintype "passive"))
      (node (ref "U7") (pin "9") (pinfunction "VREF_9") (pintype "bidirectional"))
    )
    (net (code "81") (name "unconnected-(R44-Pad4)") (class "Default")
      (node (ref "R44") (pin "4") (pinfunction "4_4") (pintype "passive"))
    )
    (net (code "82") (name "unconnected-(R44-Pad5)") (class "Default")
      (node (ref "R44") (pin "5") (pinfunction "5_5") (pintype "passive"))
    )
    (net (code "83") (name "unconnected-(U7-AUX-Pad8)") (class "Default")
      (node (ref "U7") (pin "8") (pinfunction "AUX_8") (pintype "bidirectional+no_connect"))
    )
    (net (code "84") (name "unconnected-(U7-VBAT-Pad7)") (class "Default")
      (node (ref "U7") (pin "7") (pinfunction "VBAT_7") (pintype "bidirectional+no_connect"))
    )
  )
)
